# gnss_module_evaluation_shield_schematic.net
KiCad netlist of a schematic drawn in Altium Designer
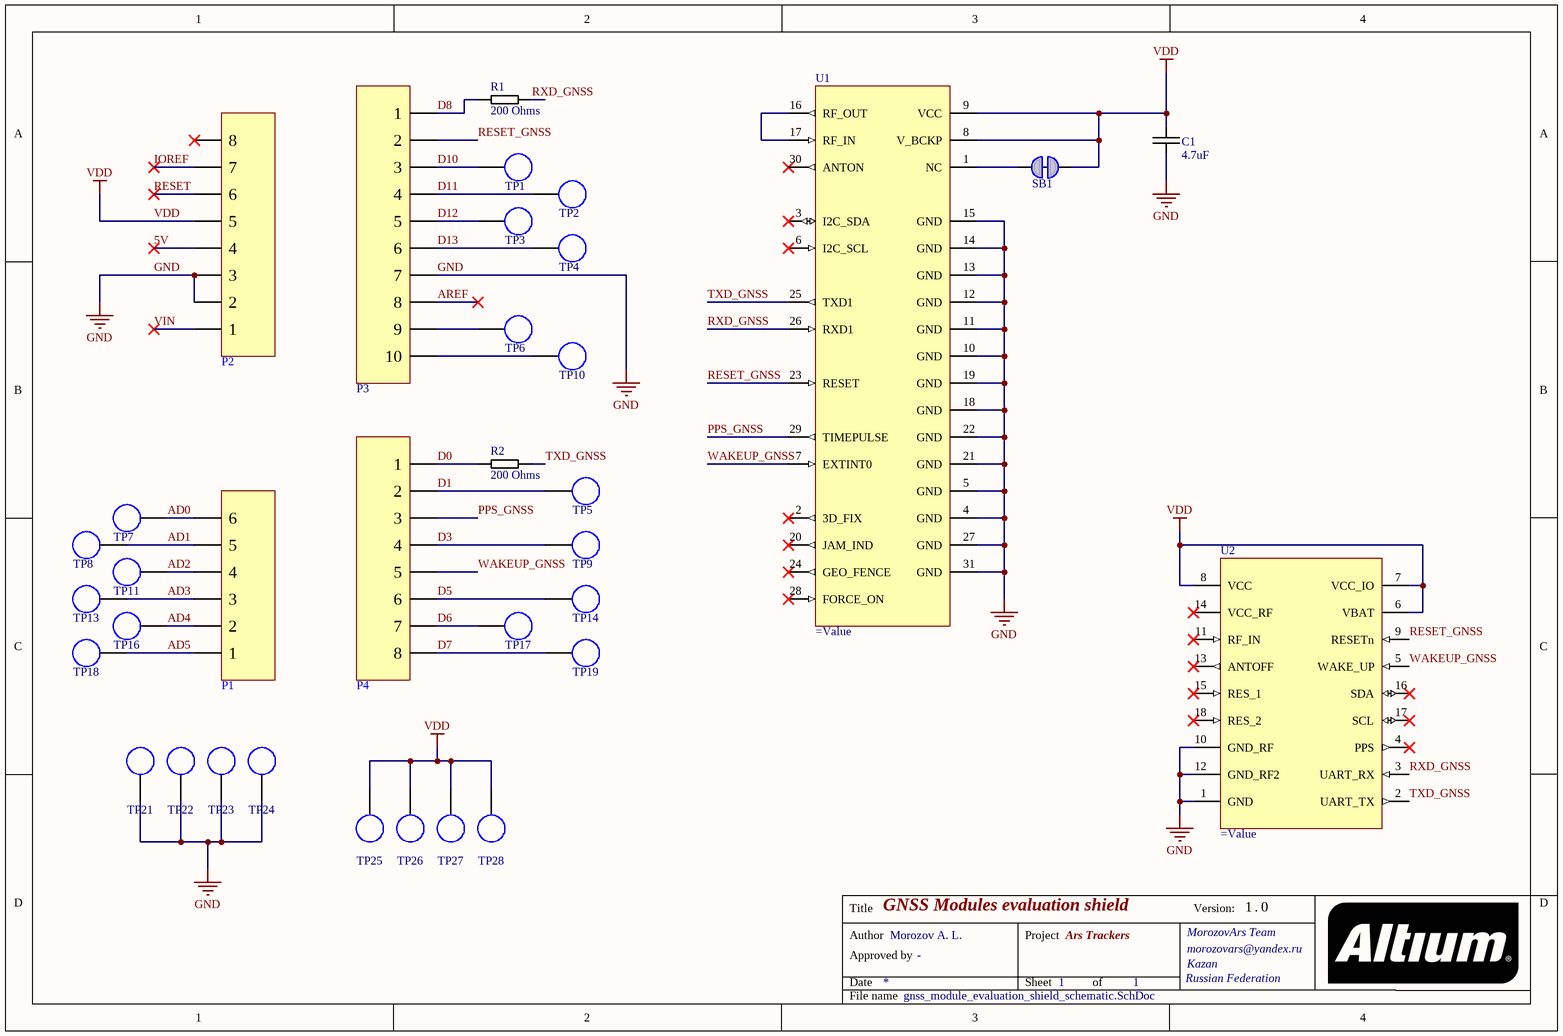
[diagram p0: gnss_module_evaluation_shield_schematic.SchDoc]

(export (version "E")
  (design (tool "Eeschema 10.0.6"))
  (components
    (comp (ref "C1")
      (value "4.7uF")
      (footprint "CAP0805")
      (description "CAP CER 4.7UF 16V X7R 0805")
      (fields
        (field (name "PART NUMBER") "GRM21BR71C475KE51L")
        (field (name "MANUFACTURER") "Murata Electronics")
        (field (name "ADDED BY") "Morozov A. L.")
      )
      (libsource (lib "Database") (part "Ceramic_capacitor"))
    )
    (comp (ref "P1")
      (value "SSQ-106-03-G-S")
      (footprint "Header 6x1 8.5mm")
      (description "CONN RCPT 6POS 0.1 GOLD PCB\r\n6 Position Receptacle Connector 0.100\" (2.54mm) Through Hole Gold")
      (fields (field (name "MANUFACTURER") "Samtech Inc.") (field (name "ADDED BY") "Morozov A. L."))
      (libsource (lib "Database") (part "CONN6"))
    )
    (comp (ref "P2")
      (value "SSQ-108-03-G-S")
      (footprint "Header 8x1 8.5mm")
      (description "CONN RCP 8POS 0.1 GOLD PCB\r\n6 Position Receptacle Connector 0.100\" (2.54mm) Through Hole Gold")
      (fields (field (name "MANUFACTURER") "Samtech Inc.") (field (name "ADDED BY") "Morozov A. L."))
      (libsource (lib "") (part "CONN8_1"))
    )
    (comp (ref "P3")
      (value "SSQ-110-03-G-S")
      (footprint "Header 10x1 8.5mm")
      (description "CONN RC 10POS 0.1 GOLD PCB\r\n6 Position Receptacle Connector 0.100\" (2.54mm) Through Hole Gold")
      (fields (field (name "MANUFACTURER") "Samtech Inc.") (field (name "ADDED BY") "Morozov A. L."))
      (libsource (lib "Database") (part "CONN10"))
    )
    (comp (ref "P4")
      (value "SSQ-108-03-G-S")
      (footprint "Header 8x1 8.5mm")
      (description "CONN RCP 8POS 0.1 GOLD PCB\r\n6 Position Receptacle Connector 0.100\" (2.54mm) Through Hole Gold")
      (fields (field (name "MANUFACTURER") "Samtech Inc.") (field (name "ADDED BY") "Morozov A. L."))
      (libsource (lib "Database") (part "CONN8"))
    )
    (comp (ref "R1")
      (value "200 Ohms")
      (footprint "R0402")
      (description "RES SMD 200 OHM 1% 1/16W 0402")
      (fields
        (field (name "PART NUMBER") "RC0402FR-07200RL")
        (field (name "MANUFACTURER") "Yageo")
        (field (name "ADDED BY") "Morozov A. L.")
      )
      (libsource (lib "Database") (part "Resistor"))
    )
    (comp (ref "R2")
      (value "200 Ohms")
      (footprint "R0402")
      (description "RES SMD 200 OHM 1% 1/16W 0402")
      (fields
        (field (name "PART NUMBER") "RC0402FR-07200RL")
        (field (name "MANUFACTURER") "Yageo")
        (field (name "ADDED BY") "Morozov A. L.")
      )
      (libsource (lib "Database") (part "Resistor"))
    )
    (comp (ref "SB1")
      (value "*")
      (footprint "Solderbridge_Shorted")
      (description "Solder bridge shorted")
      (fields (field (name "PART NUMBER") "Solderbridge shorted") (field (name "ADDED BY") "Morozov A. L."))
      (libsource (lib "Database") (part "Solderbridge Shorted"))
    )
    (comp (ref "TP1")
      (value "*")
      (footprint "TP_1MM")
      (description "Test point")
      (fields (field (name "PART NUMBER") "Test Point 1MM") (field (name "ADDED BY") "Morozov A. L."))
      (libsource (lib "Database") (part "TP"))
    )
    (comp (ref "TP2")
      (value "*")
      (footprint "TP_1MM")
      (description "Test point")
      (fields (field (name "PART NUMBER") "Test Point 1MM") (field (name "ADDED BY") "Morozov A. L."))
      (libsource (lib "Database") (part "TP"))
    )
    (comp (ref "TP3")
      (value "*")
      (footprint "TP_1MM")
      (description "Test point")
      (fields (field (name "PART NUMBER") "Test Point 1MM") (field (name "ADDED BY") "Morozov A. L."))
      (libsource (lib "Database") (part "TP"))
    )
    (comp (ref "TP4")
      (value "*")
      (footprint "TP_1MM")
      (description "Test point")
      (fields (field (name "PART NUMBER") "Test Point 1MM") (field (name "ADDED BY") "Morozov A. L."))
      (libsource (lib "Database") (part "TP"))
    )
    (comp (ref "TP5")
      (value "*")
      (footprint "TP_1MM")
      (description "Test point")
      (fields (field (name "PART NUMBER") "Test Point 1MM") (field (name "ADDED BY") "Morozov A. L."))
      (libsource (lib "Database") (part "TP"))
    )
    (comp (ref "TP6")
      (value "*")
      (footprint "TP_1MM")
      (description "Test point")
      (fields (field (name "PART NUMBER") "Test Point 1MM") (field (name "ADDED BY") "Morozov A. L."))
      (libsource (lib "Database") (part "TP"))
    )
    (comp (ref "TP7")
      (value "*")
      (footprint "TP_1MM")
      (description "Test point")
      (fields (field (name "PART NUMBER") "Test Point 1MM") (field (name "ADDED BY") "Morozov A. L."))
      (libsource (lib "Database") (part "TP"))
    )
    (comp (ref "TP8")
      (value "*")
      (footprint "TP_1MM")
      (description "Test point")
      (fields (field (name "PART NUMBER") "Test Point 1MM") (field (name "ADDED BY") "Morozov A. L."))
      (libsource (lib "Database") (part "TP"))
    )
    (comp (ref "TP9")
      (value "*")
      (footprint "TP_1MM")
      (description "Test point")
      (fields (field (name "PART NUMBER") "Test Point 1MM") (field (name "ADDED BY") "Morozov A. L."))
      (libsource (lib "Database") (part "TP"))
    )
    (comp (ref "TP10")
      (value "*")
      (footprint "TP_1MM")
      (description "Test point")
      (fields (field (name "PART NUMBER") "Test Point 1MM") (field (name "ADDED BY") "Morozov A. L."))
      (libsource (lib "Database") (part "TP"))
    )
    (comp (ref "TP11")
      (value "*")
      (footprint "TP_1MM")
      (description "Test point")
      (fields (field (name "PART NUMBER") "Test Point 1MM") (field (name "ADDED BY") "Morozov A. L."))
      (libsource (lib "Database") (part "TP"))
    )
    (comp (ref "TP13")
      (value "*")
      (footprint "TP_1MM")
      (description "Test point")
      (fields (field (name "PART NUMBER") "Test Point 1MM") (field (name "ADDED BY") "Morozov A. L."))
      (libsource (lib "Database") (part "TP"))
    )
    (comp (ref "TP14")
      (value "*")
      (footprint "TP_1MM")
      (description "Test point")
      (fields (field (name "PART NUMBER") "Test Point 1MM") (field (name "ADDED BY") "Morozov A. L."))
      (libsource (lib "Database") (part "TP"))
    )
    (comp (ref "TP16")
      (value "*")
      (footprint "TP_1MM")
      (description "Test point")
      (fields (field (name "PART NUMBER") "Test Point 1MM") (field (name "ADDED BY") "Morozov A. L."))
      (libsource (lib "Database") (part "TP"))
    )
    (comp (ref "TP17")
      (value "*")
      (footprint "TP_1MM")
      (description "Test point")
      (fields (field (name "PART NUMBER") "Test Point 1MM") (field (name "ADDED BY") "Morozov A. L."))
      (libsource (lib "Database") (part "TP"))
    )
    (comp (ref "TP18")
      (value "*")
      (footprint "TP_1MM")
      (description "Test point")
      (fields (field (name "PART NUMBER") "Test Point 1MM") (field (name "ADDED BY") "Morozov A. L."))
      (libsource (lib "Database") (part "TP"))
    )
    (comp (ref "TP19")
      (value "*")
      (footprint "TP_1MM")
      (description "Test point")
      (fields (field (name "PART NUMBER") "Test Point 1MM") (field (name "ADDED BY") "Morozov A. L."))
      (libsource (lib "Database") (part "TP"))
    )
    (comp (ref "TP21")
      (value "*")
      (footprint "TP_1MM")
      (description "Test point")
      (fields (field (name "PART NUMBER") "Test Point 1MM") (field (name "ADDED BY") "Morozov A. L."))
      (libsource (lib "Database") (part "TP"))
    )
    (comp (ref "TP22")
      (value "*")
      (footprint "TP_1MM")
      (description "Test point")
      (fields (field (name "PART NUMBER") "Test Point 1MM") (field (name "ADDED BY") "Morozov A. L."))
      (libsource (lib "Database") (part "TP"))
    )
    (comp (ref "TP23")
      (value "*")
      (footprint "TP_1MM")
      (description "Test point")
      (fields (field (name "PART NUMBER") "Test Point 1MM") (field (name "ADDED BY") "Morozov A. L."))
      (libsource (lib "Database") (part "TP"))
    )
    (comp (ref "TP24")
      (value "*")
      (footprint "TP_1MM")
      (description "Test point")
      (fields (field (name "PART NUMBER") "Test Point 1MM") (field (name "ADDED BY") "Morozov A. L."))
      (libsource (lib "Database") (part "TP"))
    )
    (comp (ref "TP25")
      (value "*")
      (footprint "TP_1MM")
      (description "Test point")
      (fields (field (name "PART NUMBER") "Test Point 1MM") (field (name "ADDED BY") "Morozov A. L."))
      (libsource (lib "Database") (part "TP"))
    )
    (comp (ref "TP26")
      (value "*")
      (footprint "TP_1MM")
      (description "Test point")
      (fields (field (name "PART NUMBER") "Test Point 1MM") (field (name "ADDED BY") "Morozov A. L."))
      (libsource (lib "Database") (part "TP"))
    )
    (comp (ref "TP27")
      (value "*")
      (footprint "TP_1MM")
      (description "Test point")
      (fields (field (name "PART NUMBER") "Test Point 1MM") (field (name "ADDED BY") "Morozov A. L."))
      (libsource (lib "Database") (part "TP"))
    )
    (comp (ref "TP28")
      (value "*")
      (footprint "TP_1MM")
      (description "Test point")
      (fields (field (name "PART NUMBER") "Test Point 1MM") (field (name "ADDED BY") "Morozov A. L."))
      (libsource (lib "Database") (part "TP"))
    )
    (comp (ref "U1")
      (value "~")
      (footprint "LCC-31")
      (fields
        (field (name "PART NUMBER") "L96-M33")
        (field (name "MANUFACTURER") "Quectel")
        (field (name "ADDED BY") "Morozov A. L.")
      )
      (libsource (lib "Database") (part "L96-M33"))
    )
    (comp (ref "U2")
      (value "~")
      (footprint "LCC-18")
      (description "BeiDou, GLONASS, GNSS, GPS 1.561GHz, 1.575MHz -163dBm   18-LCC (9.7x10.1)")
      (fields
        (field (name "PART NUMBER") "Teseo-LIV3R")
        (field (name "MANUFACTURER") "STMicroelectronics")
        (field (name "ADDED BY") "Morozov A. L.")
      )
      (libsource (lib "Database") (part "Teseo-LIV3R"))
    )
  )
  (nets
    (net (code "1") (name "/5V") (class "Default")
      (node (ref "P2") (pin "4") (pinfunction "4_4") (pintype "passive+no_connect"))
    )
    (net (code "3") (name "/AD0") (class "Default")
      (node (ref "P1") (pin "6") (pinfunction "6_6") (pintype "passive"))
      (node (ref "TP7") (pin "1") (pintype "passive"))
    )
    (net (code "4") (name "/AD1") (class "Default")
      (node (ref "P1") (pin "5") (pinfunction "5_5") (pintype "passive"))
      (node (ref "TP8") (pin "1") (pintype "passive"))
    )
    (net (code "5") (name "/AD2") (class "Default")
      (node (ref "P1") (pin "4") (pinfunction "4_4") (pintype "passive"))
      (node (ref "TP11") (pin "1") (pintype "passive"))
    )
    (net (code "6") (name "/AD3") (class "Default")
      (node (ref "P1") (pin "3") (pinfunction "3_3") (pintype "passive"))
      (node (ref "TP13") (pin "1") (pintype "passive"))
    )
    (net (code "7") (name "/AD4") (class "Default")
      (node (ref "P1") (pin "2") (pinfunction "2_2") (pintype "passive"))
      (node (ref "TP16") (pin "1") (pintype "passive"))
    )
    (net (code "8") (name "/AD5") (class "Default")
      (node (ref "P1") (pin "1") (pinfunction "1_1") (pintype "passive"))
      (node (ref "TP18") (pin "1") (pintype "passive"))
    )
    (net (code "9") (name "/AREF") (class "Default")
      (node (ref "P3") (pin "8") (pinfunction "8_8") (pintype "passive+no_connect"))
    )
    (net (code "10") (name "/D0") (class "Default")
      (node (ref "P4") (pin "1") (pinfunction "1_1") (pintype "passive"))
      (node (ref "R2") (pin "1") (pinfunction "*_1") (pintype "passive"))
    )
    (net (code "11") (name "/D1") (class "Default")
      (node (ref "P4") (pin "2") (pinfunction "2_2") (pintype "passive"))
      (node (ref "TP5") (pin "1") (pintype "passive"))
    )
    (net (code "12") (name "/D3") (class "Default")
      (node (ref "P4") (pin "4") (pinfunction "4_4") (pintype "passive"))
      (node (ref "TP9") (pin "1") (pintype "passive"))
    )
    (net (code "13") (name "/D5") (class "Default")
      (node (ref "P4") (pin "6") (pinfunction "6_6") (pintype "passive"))
      (node (ref "TP14") (pin "1") (pintype "passive"))
    )
    (net (code "14") (name "/D6") (class "Default")
      (node (ref "P4") (pin "7") (pinfunction "7_7") (pintype "passive"))
      (node (ref "TP17") (pin "1") (pintype "passive"))
    )
    (net (code "15") (name "/D7") (class "Default")
      (node (ref "P4") (pin "8") (pinfunction "8_8") (pintype "passive"))
      (node (ref "TP19") (pin "1") (pintype "passive"))
    )
    (net (code "16") (name "/D8") (class "Default")
      (node (ref "P3") (pin "1") (pinfunction "1_1") (pintype "passive"))
      (node (ref "R1") (pin "1") (pinfunction "*_1") (pintype "passive"))
    )
    (net (code "17") (name "/D10") (class "Default")
      (node (ref "P3") (pin "3") (pinfunction "3_3") (pintype "passive"))
      (node (ref "TP1") (pin "1") (pintype "passive"))
    )
    (net (code "18") (name "/D11") (class "Default")
      (node (ref "P3") (pin "4") (pinfunction "4_4") (pintype "passive"))
      (node (ref "TP2") (pin "1") (pintype "passive"))
    )
    (net (code "19") (name "/D12") (class "Default")
      (node (ref "P3") (pin "5") (pinfunction "5_5") (pintype "passive"))
      (node (ref "TP3") (pin "1") (pintype "passive"))
    )
    (net (code "20") (name "/D13") (class "Default")
      (node (ref "P3") (pin "6") (pinfunction "6_6") (pintype "passive"))
      (node (ref "TP4") (pin "1") (pintype "passive"))
    )
    (net (code "21") (name "/IOREF") (class "Default")
      (node (ref "P2") (pin "7") (pinfunction "7_7") (pintype "passive+no_connect"))
    )
    (net (code "22") (name "/PPS_GNSS") (class "Default")
      (node (ref "P4") (pin "3") (pinfunction "3_3") (pintype "passive"))
      (node (ref "U1") (pin "29") (pinfunction "TIMEPULSE_29") (pintype "output"))
    )
    (net (code "23") (name "/RESET") (class "Default")
      (node (ref "P2") (pin "6") (pinfunction "6_6") (pintype "passive+no_connect"))
    )
    (net (code "24") (name "/RESET_GNSS") (class "Default")
      (node (ref "P3") (pin "2") (pinfunction "2_2") (pintype "passive"))
      (node (ref "U1") (pin "23") (pinfunction "RESET_23") (pintype "input"))
      (node (ref "U2") (pin "9") (pinfunction "RESETn_9") (pintype "input"))
    )
    (net (code "25") (name "/RXD_GNSS") (class "Default")
      (node (ref "R1") (pin "2") (pinfunction "*_2") (pintype "passive"))
      (node (ref "U1") (pin "26") (pinfunction "RXD1_26") (pintype "input"))
      (node (ref "U2") (pin "3") (pinfunction "UART_RX_3") (pintype "input"))
    )
    (net (code "26") (name "/TXD_GNSS") (class "Default")
      (node (ref "R2") (pin "2") (pinfunction "*_2") (pintype "passive"))
      (node (ref "U1") (pin "25") (pinfunction "TXD1_25") (pintype "output"))
      (node (ref "U2") (pin "2") (pinfunction "UART_TX_2") (pintype "output"))
    )
    (net (code "27") (name "/VIN") (class "Default")
      (node (ref "P2") (pin "1") (pinfunction "1_1") (pintype "passive+no_connect"))
    )
    (net (code "28") (name "/WAKEUP_GNSS") (class "Default")
      (node (ref "P4") (pin "5") (pinfunction "5_5") (pintype "passive"))
      (node (ref "U1") (pin "7") (pinfunction "EXTINT0_7") (pintype "input"))
      (node (ref "U2") (pin "5") (pinfunction "WAKE_UP_5") (pintype "input"))
    )
    (net (code "29") (name "GND") (class "Default")
      (node (ref "C1") (pin "1") (pinfunction "*_1") (pintype "passive"))
      (node (ref "P2") (pin "2") (pinfunction "2_2") (pintype "passive"))
      (node (ref "P2") (pin "3") (pinfunction "3_3") (pintype "passive"))
      (node (ref "P3") (pin "7") (pinfunction "7_7") (pintype "passive"))
      (node (ref "TP21") (pin "1") (pintype "passive"))
      (node (ref "TP22") (pin "1") (pintype "passive"))
      (node (ref "TP23") (pin "1") (pintype "passive"))
      (node (ref "TP24") (pin "1") (pintype "passive"))
      (node (ref "U1") (pin "10") (pinfunction "GND_10") (pintype "power_in"))
      (node (ref "U1") (pin "11") (pinfunction "GND_11") (pintype "power_in"))
      (node (ref "U1") (pin "12") (pinfunction "GND_12") (pintype "power_in"))
      (node (ref "U1") (pin "13") (pinfunction "GND_13") (pintype "power_in"))
      (node (ref "U1") (pin "14") (pinfunction "GND_14") (pintype "power_in"))
      (node (ref "U1") (pin "15") (pinfunction "GND_15") (pintype "power_in"))
      (node (ref "U1") (pin "18") (pinfunction "GND_18") (pintype "power_in"))
      (node (ref "U1") (pin "19") (pinfunction "GND_19") (pintype "power_in"))
      (node (ref "U1") (pin "21") (pinfunction "GND_21") (pintype "power_in"))
      (node (ref "U1") (pin "22") (pinfunction "GND_22") (pintype "power_in"))
      (node (ref "U1") (pin "27") (pinfunction "GND_27") (pintype "power_in"))
      (node (ref "U1") (pin "31") (pinfunction "GND_31") (pintype "power_in"))
      (node (ref "U1") (pin "4") (pinfunction "GND_4") (pintype "power_in"))
      (node (ref "U1") (pin "5") (pinfunction "GND_5") (pintype "power_in"))
      (node (ref "U2") (pin "1") (pinfunction "GND_1") (pintype "power_in"))
      (node (ref "U2") (pin "10") (pinfunction "GND_RF_10") (pintype "power_in"))
      (node (ref "U2") (pin "12") (pinfunction "GND_RF2_12") (pintype "power_in"))
    )
    (net (code "30") (name "Net-(P3-Pad9)") (class "Default")
      (node (ref "P3") (pin "9") (pinfunction "9_9") (pintype "passive"))
      (node (ref "TP6") (pin "1") (pintype "passive"))
    )
    (net (code "31") (name "Net-(P3-Pad10)") (class "Default")
      (node (ref "P3") (pin "10") (pinfunction "10_10") (pintype "passive"))
      (node (ref "TP10") (pin "1") (pintype "passive"))
    )
    (net (code "32") (name "Net-(SB1-1)") (class "Default")
      (node (ref "SB1") (pin "2") (pinfunction "1_2") (pintype "passive"))
      (node (ref "U1") (pin "1") (pinfunction "NC_1") (pintype "tri_state"))
    )
    (net (code "33") (name "Net-(U1-RF_IN)") (class "Default")
      (node (ref "U1") (pin "16") (pinfunction "RF_OUT_16") (pintype "output"))
      (node (ref "U1") (pin "17") (pinfunction "RF_IN_17") (pintype "input"))
    )
    (net (code "34") (name "VDD") (class "Default")
      (node (ref "C1") (pin "2") (pinfunction "*_2") (pintype "passive"))
      (node (ref "P2") (pin "5") (pinfunction "5_5") (pintype "passive"))
      (node (ref "SB1") (pin "1") (pinfunction "0_1") (pintype "passive"))
      (node (ref "TP25") (pin "1") (pintype "passive"))
      (node (ref "TP26") (pin "1") (pintype "passive"))
      (node (ref "TP27") (pin "1") (pintype "passive"))
      (node (ref "TP28") (pin "1") (pintype "passive"))
      (node (ref "U1") (pin "8") (pinfunction "V_BCKP_8") (pintype "power_in"))
      (node (ref "U1") (pin "9") (pinfunction "VCC_9") (pintype "power_in"))
      (node (ref "U2") (pin "6") (pinfunction "VBAT_6") (pintype "power_in"))
      (node (ref "U2") (pin "7") (pinfunction "VCC_IO_7") (pintype "power_in"))
      (node (ref "U2") (pin "8") (pinfunction "VCC_8") (pintype "power_in"))
    )
    (net (code "35") (name "unconnected-(P2-Pad8)") (class "Default")
      (node (ref "P2") (pin "8") (pinfunction "8_8") (pintype "passive+no_connect"))
    )
    (net (code "36") (name "unconnected-(U1-3D_FIX-Pad2)") (class "Default")
      (node (ref "U1") (pin "2") (pinfunction "3D_FIX_2") (pintype "output+no_connect"))
    )
    (net (code "37") (name "unconnected-(U1-ANTON-Pad30)") (class "Default")
      (node (ref "U1") (pin "30") (pinfunction "ANTON_30") (pintype "output+no_connect"))
    )
    (net (code "38") (name "unconnected-(U1-FORCE_ON-Pad28)") (class "Default")
      (node (ref "U1") (pin "28") (pinfunction "FORCE_ON_28") (pintype "input+no_connect"))
    )
    (net (code "39") (name "unconnected-(U1-GEO_FENCE-Pad24)") (class "Default")
      (node (ref "U1") (pin "24") (pinfunction "GEO_FENCE_24") (pintype "output+no_connect"))
    )
    (net (code "40") (name "unconnected-(U1-I2C_SCL-Pad6)") (class "Default")
      (node (ref "U1") (pin "6") (pinfunction "I2C_SCL_6") (pintype "input+no_connect"))
    )
    (net (code "41") (name "unconnected-(U1-I2C_SDA-Pad3)") (class "Default")
      (node (ref "U1") (pin "3") (pinfunction "I2C_SDA_3") (pintype "bidirectional+no_connect"))
    )
    (net (code "42") (name "unconnected-(U1-JAM_IND-Pad20)") (class "Default")
      (node (ref "U1") (pin "20") (pinfunction "JAM_IND_20") (pintype "output+no_connect"))
    )
    (net (code "43") (name "unconnected-(U2-ANTOFF-Pad13)") (class "Default")
      (node (ref "U2") (pin "13") (pinfunction "ANTOFF_13") (pintype "output+no_connect"))
    )
    (net (code "44") (name "unconnected-(U2-PPS-Pad4)") (class "Default")
      (node (ref "U2") (pin "4") (pinfunction "PPS_4") (pintype "output+no_connect"))
    )
    (net (code "45") (name "unconnected-(U2-RES_1-Pad15)") (class "Default")
      (node (ref "U2") (pin "15") (pinfunction "RES_1_15") (pintype "input+no_connect"))
    )
    (net (code "46") (name "unconnected-(U2-RES_2-Pad18)") (class "Default")
      (node (ref "U2") (pin "18") (pinfunction "RES_2_18") (pintype "input+no_connect"))
    )
    (net (code "47") (name "unconnected-(U2-RF_IN-Pad11)") (class "Default")
      (node (ref "U2") (pin "11") (pinfunction "RF_IN_11") (pintype "input+no_connect"))
    )
    (net (code "48") (name "unconnected-(U2-SCL-Pad17)") (class "Default")
      (node (ref "U2") (pin "17") (pinfunction "SCL_17") (pintype "bidirectional+no_connect"))
    )
    (net (code "49") (name "unconnected-(U2-SDA-Pad16)") (class "Default")
      (node (ref "U2") (pin "16") (pinfunction "SDA_16") (pintype "bidirectional+no_connect"))
    )
    (net (code "50") (name "unconnected-(U2-VCC_RF-Pad14)") (class "Default")
      (node (ref "U2") (pin "14") (pinfunction "VCC_RF_14") (pintype "power_in+no_connect"))
    )
  )
)
